# Peripheral.net
KiCad netlist of a schematic drawn in Altium Designer
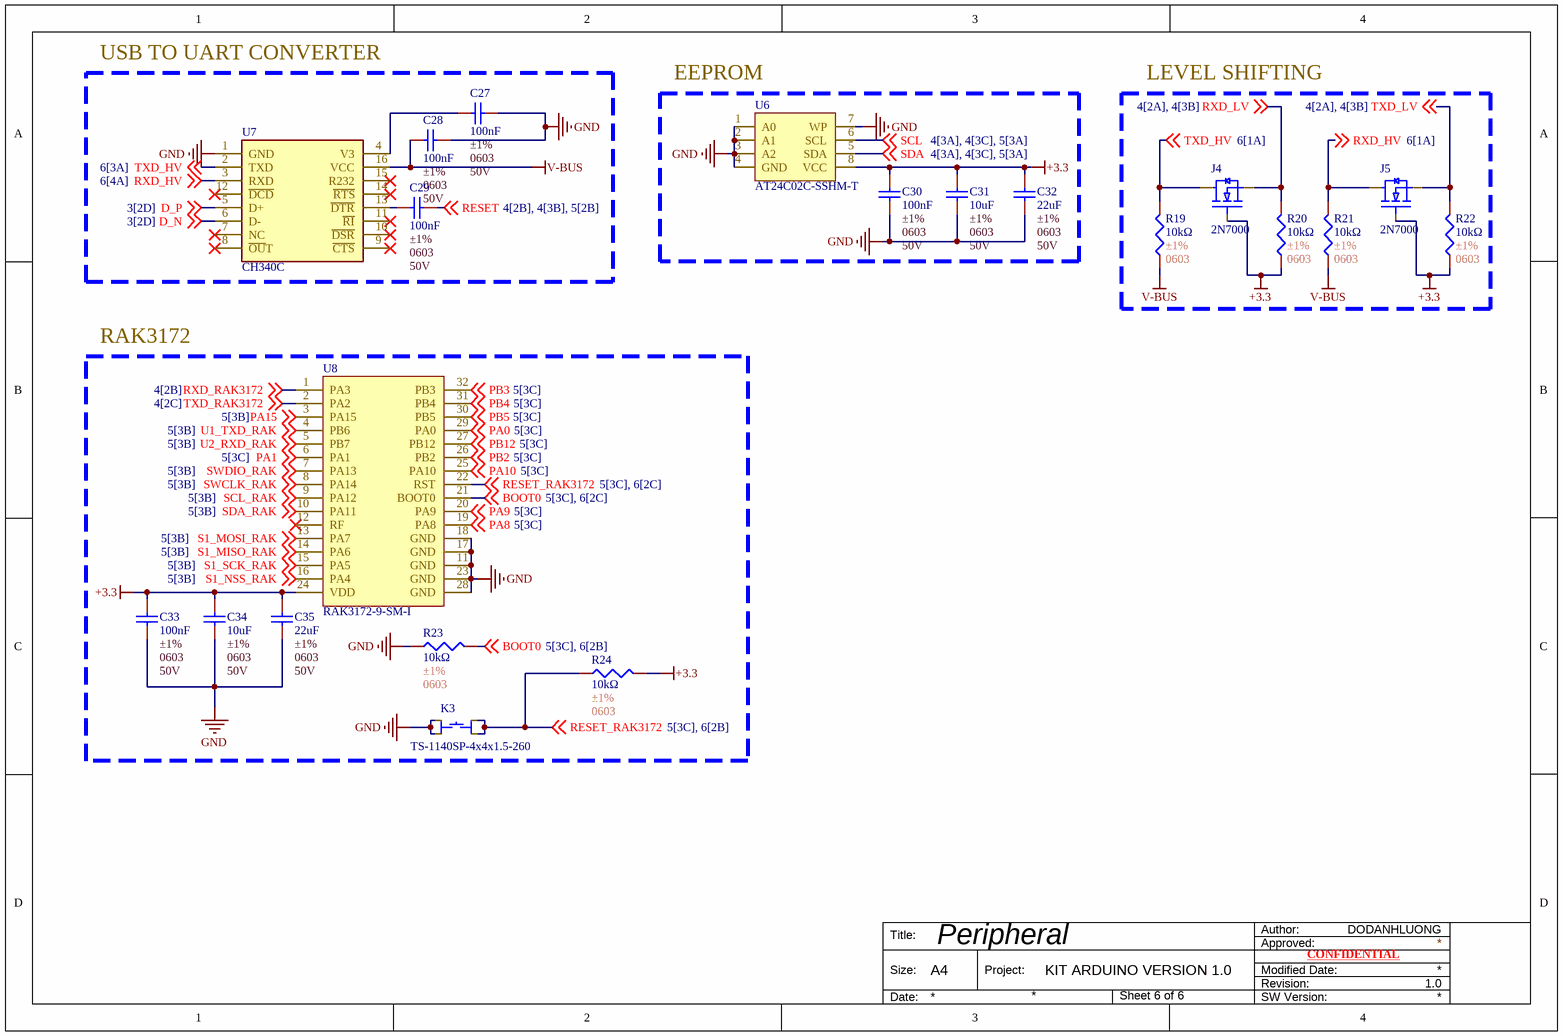
[diagram p0: Peripheral.SchDoc]

(export (version "E")
  (design (tool "Eeschema 10.0.6"))
  (components
    (comp (ref "C27")
      (value "100nF")
      (footprint "C0603")
      (description "50V 10pF NP0 ±1% 0402 Multilayer Ceramic Capacitors MLCC - SMD/SMT ROHS")
      (fields
        (field (name "MANUFACTURER") "YAGEO")
        (field (name "MFR. PART #") "CC0402FRNPO9BN100")
        (field (name "TOLERANCE") "±1%")
        (field (name "PACKAGE") "0603")
        (field (name "VOLTAGE RATING") "50V")
      )
      (libsource (lib "Capital") (part "C0603_100nF_±1%"))
    )
    (comp (ref "C28")
      (value "100nF")
      (footprint "C0603")
      (description "50V 10pF NP0 ±1% 0402 Multilayer Ceramic Capacitors MLCC - SMD/SMT ROHS")
      (fields
        (field (name "MANUFACTURER") "YAGEO")
        (field (name "MFR. PART #") "CC0402FRNPO9BN100")
        (field (name "TOLERANCE") "±1%")
        (field (name "PACKAGE") "0603")
        (field (name "VOLTAGE RATING") "50V")
      )
      (libsource (lib "Capital") (part "C0603_100nF_±1%"))
    )
    (comp (ref "C29")
      (value "100nF")
      (footprint "C0603")
      (description "50V 10pF NP0 ±1% 0402 Multilayer Ceramic Capacitors MLCC - SMD/SMT ROHS")
      (fields
        (field (name "MANUFACTURER") "YAGEO")
        (field (name "MFR. PART #") "CC0402FRNPO9BN100")
        (field (name "TOLERANCE") "±1%")
        (field (name "PACKAGE") "0603")
        (field (name "VOLTAGE RATING") "50V")
      )
      (libsource (lib "Capital") (part "C0603_100nF_±1%"))
    )
    (comp (ref "C30")
      (value "100nF")
      (footprint "C0603")
      (description "50V 10pF NP0 ±1% 0402 Multilayer Ceramic Capacitors MLCC - SMD/SMT ROHS")
      (fields
        (field (name "MANUFACTURER") "YAGEO")
        (field (name "MFR. PART #") "CC0402FRNPO9BN100")
        (field (name "TOLERANCE") "±1%")
        (field (name "PACKAGE") "0603")
        (field (name "VOLTAGE RATING") "50V")
      )
      (libsource (lib "Capital") (part "C0603_100nF_±1%"))
    )
    (comp (ref "C31")
      (value "10uF")
      (footprint "C0603")
      (description "50V 10pF NP0 ±1% 0402 Multilayer Ceramic Capacitors MLCC - SMD/SMT ROHS")
      (fields
        (field (name "MANUFACTURER") "YAGEO")
        (field (name "MFR. PART #") "CC0402FRNPO9BN100")
        (field (name "TOLERANCE") "±1%")
        (field (name "PACKAGE") "0603")
        (field (name "VOLTAGE RATING") "50V")
      )
      (libsource (lib "Capital") (part "C0603_10uF_±1%"))
    )
    (comp (ref "C32")
      (value "22uF")
      (footprint "C0603")
      (description "50V 10pF NP0 ±1% 0402 Multilayer Ceramic Capacitors MLCC - SMD/SMT ROHS")
      (fields
        (field (name "MANUFACTURER") "YAGEO")
        (field (name "MFR. PART #") "CC0402FRNPO9BN100")
        (field (name "TOLERANCE") "±1%")
        (field (name "PACKAGE") "0603")
        (field (name "VOLTAGE RATING") "50V")
      )
      (libsource (lib "Capital") (part "C0603_22uF_±1%"))
    )
    (comp (ref "C33")
      (value "100nF")
      (footprint "C0603")
      (description "50V 10pF NP0 ±1% 0402 Multilayer Ceramic Capacitors MLCC - SMD/SMT ROHS")
      (fields
        (field (name "MANUFACTURER") "YAGEO")
        (field (name "MFR. PART #") "CC0402FRNPO9BN100")
        (field (name "TOLERANCE") "±1%")
        (field (name "PACKAGE") "0603")
        (field (name "VOLTAGE RATING") "50V")
      )
      (libsource (lib "Capital") (part "C0603_100nF_±1%"))
    )
    (comp (ref "C34")
      (value "10uF")
      (footprint "C0603")
      (description "50V 10pF NP0 ±1% 0402 Multilayer Ceramic Capacitors MLCC - SMD/SMT ROHS")
      (fields
        (field (name "MANUFACTURER") "YAGEO")
        (field (name "MFR. PART #") "CC0402FRNPO9BN100")
        (field (name "TOLERANCE") "±1%")
        (field (name "PACKAGE") "0603")
        (field (name "VOLTAGE RATING") "50V")
      )
      (libsource (lib "Capital") (part "C0603_10uF_±1%"))
    )
    (comp (ref "C35")
      (value "22uF")
      (footprint "C0603")
      (description "50V 10pF NP0 ±1% 0402 Multilayer Ceramic Capacitors MLCC - SMD/SMT ROHS")
      (fields
        (field (name "MANUFACTURER") "YAGEO")
        (field (name "MFR. PART #") "CC0402FRNPO9BN100")
        (field (name "TOLERANCE") "±1%")
        (field (name "PACKAGE") "0603")
        (field (name "VOLTAGE RATING") "50V")
      )
      (libsource (lib "Capital") (part "C0603_22uF_±1%"))
    )
    (comp (ref "J4")
      (value "2N7000")
      (footprint "2N7000")
      (description "60V 200mA 400mW 5Ω@10V 3V@1mA 1 N-Channel TO-92-3L MOSFETs ROHS")
      (fields (field (name "MANUFACTURER") "onsemi") (field (name "LCSC PART #") "C232838"))
      (libsource (lib "Mosfet") (part "2N7000"))
    )
    (comp (ref "J5")
      (value "2N7000")
      (footprint "2N7000")
      (description "60V 200mA 400mW 5Ω@10V 3V@1mA 1 N-Channel TO-92-3L MOSFETs ROHS")
      (fields (field (name "MANUFACTURER") "onsemi") (field (name "LCSC PART #") "C232838"))
      (libsource (lib "Mosfet") (part "2N7000"))
    )
    (comp (ref "K3")
      (value "TS-1140SP-4x4x1.5-260")
      (footprint "4x4x1.5")
      (description "SMD Tactile Switches ROHS")
      (fields (field (name "MANUFACTURER") "CAX") (field (name "LCSC PART #") "C49023394"))
      (libsource (lib "Switch") (part "TS-1140SP-4x4x1.5-260"))
    )
    (comp (ref "R19")
      (value "10kΩ")
      (footprint "R0603")
      (description "62.5mW Thick Film Resistor 50V ±1% ±200ppm/℃ 10Ω 0402 Chip Resistor - Surface Mount ROHS")
      (fields
        (field (name "MANUFACTURER") "YAGEO")
        (field (name "MFR. PART #") "RC0402FR-0710RL")
        (field (name "TOLERANCE") "±1%")
        (field (name "PACKAGE") "0603")
      )
      (libsource (lib "Resistor") (part "R0603_10kΩ_±1%"))
    )
    (comp (ref "R20")
      (value "10kΩ")
      (footprint "R0603")
      (description "62.5mW Thick Film Resistor 50V ±1% ±200ppm/℃ 10Ω 0402 Chip Resistor - Surface Mount ROHS")
      (fields
        (field (name "MANUFACTURER") "YAGEO")
        (field (name "MFR. PART #") "RC0402FR-0710RL")
        (field (name "TOLERANCE") "±1%")
        (field (name "PACKAGE") "0603")
      )
      (libsource (lib "Resistor") (part "R0603_10kΩ_±1%"))
    )
    (comp (ref "R21")
      (value "10kΩ")
      (footprint "R0603")
      (description "62.5mW Thick Film Resistor 50V ±1% ±200ppm/℃ 10Ω 0402 Chip Resistor - Surface Mount ROHS")
      (fields
        (field (name "MANUFACTURER") "YAGEO")
        (field (name "MFR. PART #") "RC0402FR-0710RL")
        (field (name "TOLERANCE") "±1%")
        (field (name "PACKAGE") "0603")
      )
      (libsource (lib "Resistor") (part "R0603_10kΩ_±1%"))
    )
    (comp (ref "R22")
      (value "10kΩ")
      (footprint "R0603")
      (description "62.5mW Thick Film Resistor 50V ±1% ±200ppm/℃ 10Ω 0402 Chip Resistor - Surface Mount ROHS")
      (fields
        (field (name "MANUFACTURER") "YAGEO")
        (field (name "MFR. PART #") "RC0402FR-0710RL")
        (field (name "TOLERANCE") "±1%")
        (field (name "PACKAGE") "0603")
      )
      (libsource (lib "Resistor") (part "R0603_10kΩ_±1%"))
    )
    (comp (ref "R23")
      (value "10kΩ")
      (footprint "R0603")
      (description "62.5mW Thick Film Resistor 50V ±1% ±200ppm/℃ 10Ω 0402 Chip Resistor - Surface Mount ROHS")
      (fields
        (field (name "MANUFACTURER") "YAGEO")
        (field (name "MFR. PART #") "RC0402FR-0710RL")
        (field (name "TOLERANCE") "±1%")
        (field (name "PACKAGE") "0603")
      )
      (libsource (lib "Resistor") (part "R0603_10kΩ_±1%"))
    )
    (comp (ref "R24")
      (value "10kΩ")
      (footprint "R0603")
      (description "62.5mW Thick Film Resistor 50V ±1% ±200ppm/℃ 10Ω 0402 Chip Resistor - Surface Mount ROHS")
      (fields
        (field (name "MANUFACTURER") "YAGEO")
        (field (name "MFR. PART #") "RC0402FR-0710RL")
        (field (name "TOLERANCE") "±1%")
        (field (name "PACKAGE") "0603")
      )
      (libsource (lib "Resistor") (part "R0603_10kΩ_±1%"))
    )
    (comp (ref "U6")
      (value "AT24C02C-SSHM-T")
      (footprint "AT24C02C-SSHM-T")
      (description "2Kbit 1MHz I2C SOIC-8 EEPROM ROHS")
      (fields (field (name "MANUFACTURER") "MICROCHIP") (field (name "LCSC PART #") "C6203"))
      (libsource (lib "IC") (part "AT24C02C-SSHM-T"))
    )
    (comp (ref "U7")
      (value "CH340C")
      (footprint "CH340C")
      (description "2Mbps Transceiver USB 2.0 SOP-16 USB Converters ROHS")
      (fields (field (name "MANUFACTURER") "WCH") (field (name "LCSC PART #") "C84681"))
      (libsource (lib "IC") (part "CH340C"))
    )
    (comp (ref "U8")
      (value "RAK3172-9-SM-I")
      (footprint "RAK3172-9-SM-I")
      (description "15km SMD,15.5x15mm LoRa Modules ROHS")
      (fields (field (name "LCSC PART #") "C19723905") (field (name "MANUFACTURER") "RAKwireless"))
      (libsource (lib "MCU") (part "RAK3172-9-SM-I"))
    )
  )
  (nets
    (net (code "1") (name "+3.3") (class "Default")
      (node (ref "C30") (pin "1") (pinfunction "1_1") (pintype "passive"))
      (node (ref "C31") (pin "1") (pinfunction "1_1") (pintype "passive"))
      (node (ref "C32") (pin "1") (pinfunction "1_1") (pintype "passive"))
      (node (ref "C33") (pin "1") (pinfunction "1_1") (pintype "passive"))
      (node (ref "C34") (pin "1") (pinfunction "1_1") (pintype "passive"))
      (node (ref "C35") (pin "1") (pinfunction "1_1") (pintype "passive"))
      (node (ref "J4") (pin "2") (pinfunction "G_2") (pintype "passive"))
      (node (ref "J5") (pin "2") (pinfunction "G_2") (pintype "passive"))
      (node (ref "R20") (pin "1") (pinfunction "1_1") (pintype "passive"))
      (node (ref "R22") (pin "1") (pinfunction "1_1") (pintype "passive"))
      (node (ref "R24") (pin "2") (pinfunction "2_2") (pintype "passive"))
      (node (ref "U6") (pin "8") (pinfunction "VCC_8") (pintype "passive"))
      (node (ref "U8") (pin "24") (pinfunction "VDD_24") (pintype "passive"))
    )
    (net (code "2") (name "BOOT0") (class "Default")
      (node (ref "R23") (pin "2") (pinfunction "2_2") (pintype "passive"))
      (node (ref "U8") (pin "21") (pinfunction "BOOT0_21") (pintype "passive"))
    )
    (net (code "3") (name "D_N") (class "Default")
      (node (ref "U7") (pin "6") (pinfunction "D-_6") (pintype "passive"))
    )
    (net (code "4") (name "D_P") (class "Default")
      (node (ref "U7") (pin "5") (pinfunction "D+_5") (pintype "passive"))
    )
    (net (code "5") (name "GND") (class "Default")
      (node (ref "C27") (pin "2") (pinfunction "2_2") (pintype "passive"))
      (node (ref "C28") (pin "2") (pinfunction "2_2") (pintype "passive"))
      (node (ref "C30") (pin "2") (pinfunction "2_2") (pintype "passive"))
      (node (ref "C31") (pin "2") (pinfunction "2_2") (pintype "passive"))
      (node (ref "C32") (pin "2") (pinfunction "2_2") (pintype "passive"))
      (node (ref "C33") (pin "2") (pinfunction "2_2") (pintype "passive"))
      (node (ref "C34") (pin "2") (pinfunction "2_2") (pintype "passive"))
      (node (ref "C35") (pin "2") (pinfunction "2_2") (pintype "passive"))
      (node (ref "K3") (pin "1") (pinfunction "1_1") (pintype "passive"))
      (node (ref "K3") (pin "3") (pinfunction "3_3") (pintype "passive"))
      (node (ref "R23") (pin "1") (pinfunction "1_1") (pintype "passive"))
      (node (ref "U6") (pin "1") (pinfunction "A0_1") (pintype "passive"))
      (node (ref "U6") (pin "2") (pinfunction "A1_2") (pintype "passive"))
      (node (ref "U6") (pin "3") (pinfunction "A2_3") (pintype "passive"))
      (node (ref "U6") (pin "4") (pinfunction "GND_4") (pintype "passive"))
      (node (ref "U6") (pin "7") (pinfunction "WP_7") (pintype "passive"))
      (node (ref "U7") (pin "1") (pinfunction "GND_1") (pintype "passive"))
      (node (ref "U8") (pin "11") (pinfunction "GND_11") (pintype "passive"))
      (node (ref "U8") (pin "17") (pinfunction "GND_17") (pintype "passive"))
      (node (ref "U8") (pin "18") (pinfunction "GND_18") (pintype "passive"))
      (node (ref "U8") (pin "23") (pinfunction "GND_23") (pintype "passive"))
      (node (ref "U8") (pin "28") (pinfunction "GND_28") (pintype "passive"))
    )
    (net (code "6") (name "Net-(U7-V3)") (class "Default")
      (node (ref "C27") (pin "1") (pinfunction "1_1") (pintype "passive"))
      (node (ref "U7") (pin "4") (pinfunction "V3_4") (pintype "passive"))
    )
    (net (code "7") (name "Net-(U7-~{DTR})") (class "Default")
      (node (ref "C29") (pin "1") (pinfunction "1_1") (pintype "passive"))
      (node (ref "U7") (pin "13") (pinfunction "~{DTR}_13") (pintype "passive"))
    )
    (net (code "8") (name "PA0") (class "Default")
      (node (ref "U8") (pin "29") (pinfunction "PA0_29") (pintype "passive"))
    )
    (net (code "9") (name "PA1") (class "Default")
      (node (ref "U8") (pin "6") (pinfunction "PA1_6") (pintype "passive"))
    )
    (net (code "10") (name "PA8") (class "Default")
      (node (ref "U8") (pin "19") (pinfunction "PA8_19") (pintype "passive"))
    )
    (net (code "11") (name "PA9") (class "Default")
      (node (ref "U8") (pin "20") (pinfunction "PA9_20") (pintype "passive"))
    )
    (net (code "12") (name "PA10") (class "Default")
      (node (ref "U8") (pin "25") (pinfunction "PA10_25") (pintype "passive"))
    )
    (net (code "13") (name "PA15") (class "Default")
      (node (ref "U8") (pin "3") (pinfunction "PA15_3") (pintype "passive"))
    )
    (net (code "14") (name "PB2") (class "Default")
      (node (ref "U8") (pin "26") (pinfunction "PB2_26") (pintype "passive"))
    )
    (net (code "15") (name "PB3") (class "Default")
      (node (ref "U8") (pin "32") (pinfunction "PB3_32") (pintype "passive"))
    )
    (net (code "16") (name "PB4") (class "Default")
      (node (ref "U8") (pin "31") (pinfunction "PB4_31") (pintype "passive"))
    )
    (net (code "17") (name "PB5") (class "Default")
      (node (ref "U8") (pin "30") (pinfunction "PB5_30") (pintype "passive"))
    )
    (net (code "18") (name "PB12") (class "Default")
      (node (ref "U8") (pin "27") (pinfunction "PB12_27") (pintype "passive"))
    )
    (net (code "19") (name "RESET") (class "Default")
      (node (ref "C29") (pin "2") (pinfunction "2_2") (pintype "passive"))
    )
    (net (code "20") (name "RESET_RAK3172") (class "Default")
      (node (ref "K3") (pin "2") (pinfunction "2_2") (pintype "passive"))
      (node (ref "K3") (pin "4") (pinfunction "4_4") (pintype "passive"))
      (node (ref "R24") (pin "1") (pinfunction "1_1") (pintype "passive"))
      (node (ref "U8") (pin "22") (pinfunction "RST_22") (pintype "passive"))
    )
    (net (code "21") (name "RXD_HV") (class "Default")
      (node (ref "J5") (pin "3") (pinfunction "D_3") (pintype "passive"))
      (node (ref "R21") (pin "2") (pinfunction "2_2") (pintype "passive"))
      (node (ref "U7") (pin "3") (pinfunction "RXD_3") (pintype "passive"))
    )
    (net (code "22") (name "RXD_LV") (class "Default")
      (node (ref "J4") (pin "1") (pinfunction "S_1") (pintype "passive"))
      (node (ref "R20") (pin "2") (pinfunction "2_2") (pintype "passive"))
    )
    (net (code "23") (name "RXD_RAK3172") (class "Default")
      (node (ref "U8") (pin "1") (pinfunction "PA3_1") (pintype "passive"))
    )
    (net (code "24") (name "S1_MISO_RAK") (class "Default")
      (node (ref "U8") (pin "14") (pinfunction "PA6_14") (pintype "passive"))
    )
    (net (code "25") (name "S1_MOSI_RAK") (class "Default")
      (node (ref "U8") (pin "13") (pinfunction "PA7_13") (pintype "passive"))
    )
    (net (code "26") (name "S1_NSS_RAK") (class "Default")
      (node (ref "U8") (pin "16") (pinfunction "PA4_16") (pintype "passive"))
    )
    (net (code "27") (name "S1_SCK_RAK") (class "Default")
      (node (ref "U8") (pin "15") (pinfunction "PA5_15") (pintype "passive"))
    )
    (net (code "28") (name "SCL") (class "Default")
      (node (ref "U6") (pin "6") (pinfunction "SCL_6") (pintype "passive"))
    )
    (net (code "29") (name "SCL_RAK") (class "Default")
      (node (ref "U8") (pin "9") (pinfunction "PA12_9") (pintype "passive"))
    )
    (net (code "30") (name "SDA") (class "Default")
      (node (ref "U6") (pin "5") (pinfunction "SDA_5") (pintype "passive"))
    )
    (net (code "31") (name "SDA_RAK") (class "Default")
      (node (ref "U8") (pin "10") (pinfunction "PA11_10") (pintype "passive"))
    )
    (net (code "32") (name "SWCLK_RAK") (class "Default")
      (node (ref "U8") (pin "8") (pinfunction "PA14_8") (pintype "passive"))
    )
    (net (code "33") (name "SWDIO_RAK") (class "Default")
      (node (ref "U8") (pin "7") (pinfunction "PA13_7") (pintype "passive"))
    )
    (net (code "34") (name "TXD_HV") (class "Default")
      (node (ref "J4") (pin "3") (pinfunction "D_3") (pintype "passive"))
      (node (ref "R19") (pin "2") (pinfunction "2_2") (pintype "passive"))
      (node (ref "U7") (pin "2") (pinfunction "TXD_2") (pintype "passive"))
    )
    (net (code "35") (name "TXD_LV") (class "Default")
      (node (ref "J5") (pin "1") (pinfunction "S_1") (pintype "passive"))
      (node (ref "R22") (pin "2") (pinfunction "2_2") (pintype "passive"))
    )
    (net (code "36") (name "TXD_RAK3172") (class "Default")
      (node (ref "U8") (pin "2") (pinfunction "PA2_2") (pintype "passive"))
    )
    (net (code "37") (name "U1_TXD_RAK") (class "Default")
      (node (ref "U8") (pin "4") (pinfunction "PB6_4") (pintype "passive"))
    )
    (net (code "38") (name "U2_RXD_RAK") (class "Default")
      (node (ref "U8") (pin "5") (pinfunction "PB7_5") (pintype "passive"))
    )
    (net (code "39") (name "V-BUS") (class "Default")
      (node (ref "C28") (pin "1") (pinfunction "1_1") (pintype "passive"))
      (node (ref "R19") (pin "1") (pinfunction "1_1") (pintype "passive"))
      (node (ref "R21") (pin "1") (pinfunction "1_1") (pintype "passive"))
      (node (ref "U7") (pin "16") (pinfunction "VCC_16") (pintype "passive"))
    )
    (net (code "40") (name "unconnected-(U7-NC-Pad7)") (class "Default")
      (node (ref "U7") (pin "7") (pinfunction "NC_7") (pintype "passive+no_connect"))
    )
    (net (code "41") (name "unconnected-(U7-R232-Pad15)") (class "Default")
      (node (ref "U7") (pin "15") (pinfunction "R232_15") (pintype "passive+no_connect"))
    )
    (net (code "42") (name "unconnected-(U7-~{CTS}-Pad9)") (class "Default")
      (node (ref "U7") (pin "9") (pinfunction "~{CTS}_9") (pintype "passive+no_connect"))
    )
    (net (code "43") (name "unconnected-(U7-~{DCD}-Pad12)") (class "Default")
      (node (ref "U7") (pin "12") (pinfunction "~{DCD}_12") (pintype "passive+no_connect"))
    )
    (net (code "44") (name "unconnected-(U7-~{DSR}-Pad10)") (class "Default")
      (node (ref "U7") (pin "10") (pinfunction "~{DSR}_10") (pintype "passive+no_connect"))
    )
    (net (code "45") (name "unconnected-(U7-~{OU}T-Pad8)") (class "Default")
      (node (ref "U7") (pin "8") (pinfunction "~{OU}T_8") (pintype "passive+no_connect"))
    )
    (net (code "46") (name "unconnected-(U7-~{RI}-Pad11)") (class "Default")
      (node (ref "U7") (pin "11") (pinfunction "~{RI}_11") (pintype "passive+no_connect"))
    )
    (net (code "47") (name "unconnected-(U7-~{RTS}-Pad14)") (class "Default")
      (node (ref "U7") (pin "14") (pinfunction "~{RTS}_14") (pintype "passive+no_connect"))
    )
    (net (code "48") (name "unconnected-(U8-RF-Pad12)") (class "Default")
      (node (ref "U8") (pin "12") (pinfunction "RF_12") (pintype "passive+no_connect"))
    )
  )
)
